# RTDsSheet2.net
KiCad netlist of a schematic drawn in Altium Designer
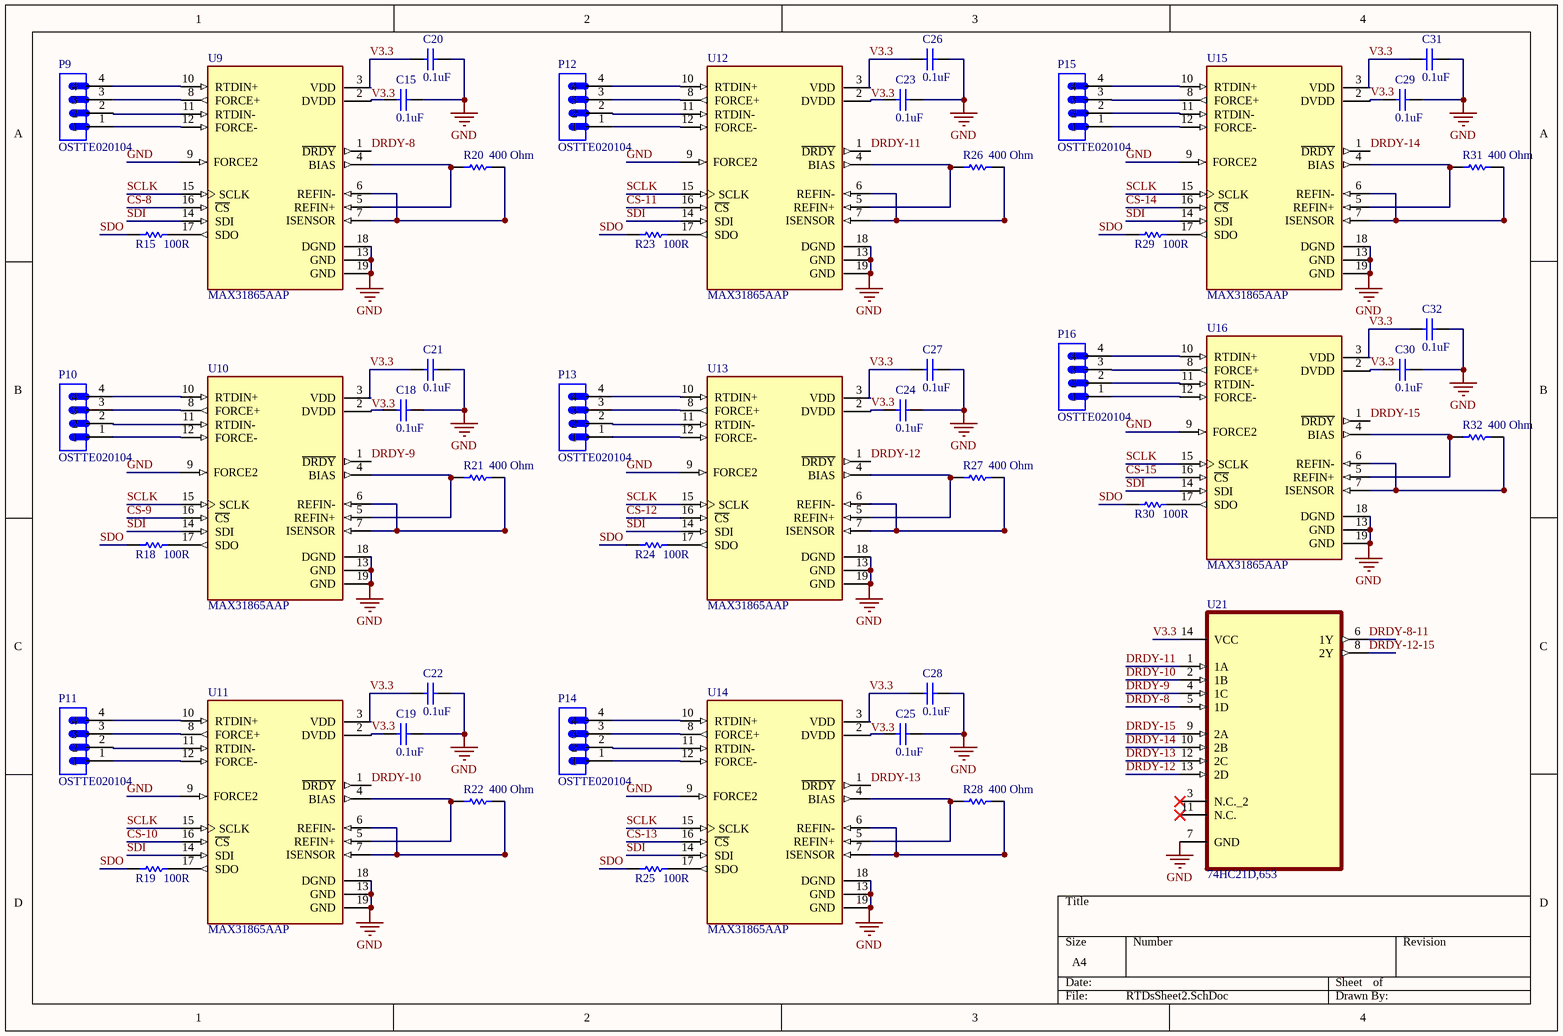
[diagram p0: RTDsSheet2.SchDoc]

(export (version "E")
  (design (tool "Eeschema 10.0.6"))
  (components
    (comp (ref "C15")
      (value "0.1uF")
      (footprint "1608[0603]")
      (description "Capacitor (Semiconductor SIM Model)")
      (fields (field (name "PUBLISHER") "Altium Limited"))
      (libsource (lib "Miscellaneous Devices") (part "Cap Semi"))
    )
    (comp (ref "C18")
      (value "0.1uF")
      (footprint "1608[0603]")
      (description "Capacitor (Semiconductor SIM Model)")
      (fields (field (name "PUBLISHER") "Altium Limited"))
      (libsource (lib "Miscellaneous Devices") (part "Cap Semi"))
    )
    (comp (ref "C19")
      (value "0.1uF")
      (footprint "1608[0603]")
      (description "Capacitor (Semiconductor SIM Model)")
      (fields (field (name "PUBLISHER") "Altium Limited"))
      (libsource (lib "Miscellaneous Devices") (part "Cap Semi"))
    )
    (comp (ref "C20")
      (value "0.1uF")
      (footprint "1608[0603]")
      (description "Capacitor (Semiconductor SIM Model)")
      (fields (field (name "PUBLISHER") "Altium Limited"))
      (libsource (lib "Miscellaneous Devices") (part "Cap Semi"))
    )
    (comp (ref "C21")
      (value "0.1uF")
      (footprint "1608[0603]")
      (description "Capacitor (Semiconductor SIM Model)")
      (fields (field (name "PUBLISHER") "Altium Limited"))
      (libsource (lib "Miscellaneous Devices") (part "Cap Semi"))
    )
    (comp (ref "C22")
      (value "0.1uF")
      (footprint "1608[0603]")
      (description "Capacitor (Semiconductor SIM Model)")
      (fields (field (name "PUBLISHER") "Altium Limited"))
      (libsource (lib "Miscellaneous Devices") (part "Cap Semi"))
    )
    (comp (ref "C23")
      (value "0.1uF")
      (footprint "1608[0603]")
      (description "Capacitor (Semiconductor SIM Model)")
      (fields (field (name "PUBLISHER") "Altium Limited"))
      (libsource (lib "Miscellaneous Devices") (part "Cap Semi"))
    )
    (comp (ref "C24")
      (value "0.1uF")
      (footprint "1608[0603]")
      (description "Capacitor (Semiconductor SIM Model)")
      (fields (field (name "PUBLISHER") "Altium Limited"))
      (libsource (lib "Miscellaneous Devices") (part "Cap Semi"))
    )
    (comp (ref "C25")
      (value "0.1uF")
      (footprint "1608[0603]")
      (description "Capacitor (Semiconductor SIM Model)")
      (fields (field (name "PUBLISHER") "Altium Limited"))
      (libsource (lib "Miscellaneous Devices") (part "Cap Semi"))
    )
    (comp (ref "C26")
      (value "0.1uF")
      (footprint "1608[0603]")
      (description "Capacitor (Semiconductor SIM Model)")
      (fields (field (name "PUBLISHER") "Altium Limited"))
      (libsource (lib "Miscellaneous Devices") (part "Cap Semi"))
    )
    (comp (ref "C27")
      (value "0.1uF")
      (footprint "1608[0603]")
      (description "Capacitor (Semiconductor SIM Model)")
      (fields (field (name "PUBLISHER") "Altium Limited"))
      (libsource (lib "Miscellaneous Devices") (part "Cap Semi"))
    )
    (comp (ref "C28")
      (value "0.1uF")
      (footprint "1608[0603]")
      (description "Capacitor (Semiconductor SIM Model)")
      (fields (field (name "PUBLISHER") "Altium Limited"))
      (libsource (lib "Miscellaneous Devices") (part "Cap Semi"))
    )
    (comp (ref "C29")
      (value "0.1uF")
      (footprint "1608[0603]")
      (description "Capacitor (Semiconductor SIM Model)")
      (fields (field (name "PUBLISHER") "Altium Limited"))
      (libsource (lib "Miscellaneous Devices") (part "Cap Semi"))
    )
    (comp (ref "C30")
      (value "0.1uF")
      (footprint "1608[0603]")
      (description "Capacitor (Semiconductor SIM Model)")
      (fields (field (name "PUBLISHER") "Altium Limited"))
      (libsource (lib "Miscellaneous Devices") (part "Cap Semi"))
    )
    (comp (ref "C31")
      (value "0.1uF")
      (footprint "1608[0603]")
      (description "Capacitor (Semiconductor SIM Model)")
      (fields (field (name "PUBLISHER") "Altium Limited"))
      (libsource (lib "Miscellaneous Devices") (part "Cap Semi"))
    )
    (comp (ref "C32")
      (value "0.1uF")
      (footprint "1608[0603]")
      (description "Capacitor (Semiconductor SIM Model)")
      (fields (field (name "PUBLISHER") "Altium Limited"))
      (libsource (lib "Miscellaneous Devices") (part "Cap Semi"))
    )
    (comp (ref "P9")
      (value "OSTTE020104")
      (footprint "3-641209-4:TE_3-641209-4")
      (description "Terminal Block 3.5mm 2pos Pcb")
      (fields (field (name "MF") "{'manufacturer': u'On Shore'}"))
      (libsource (lib "OSTTE040104") (part "OSTTE020104"))
    )
    (comp (ref "P10")
      (value "OSTTE020104")
      (footprint "3-641209-4:TE_3-641209-4")
      (description "Terminal Block 3.5mm 2pos Pcb")
      (fields (field (name "MF") "{'manufacturer': u'On Shore'}"))
      (libsource (lib "OSTTE040104") (part "OSTTE020104"))
    )
    (comp (ref "P11")
      (value "OSTTE020104")
      (footprint "3-641209-4:TE_3-641209-4")
      (description "Terminal Block 3.5mm 2pos Pcb")
      (fields (field (name "MF") "{'manufacturer': u'On Shore'}"))
      (libsource (lib "OSTTE040104") (part "OSTTE020104"))
    )
    (comp (ref "P12")
      (value "OSTTE020104")
      (footprint "3-641209-4:TE_3-641209-4")
      (description "Terminal Block 3.5mm 2pos Pcb")
      (fields (field (name "MF") "{'manufacturer': u'On Shore'}"))
      (libsource (lib "OSTTE040104") (part "OSTTE020104"))
    )
    (comp (ref "P13")
      (value "OSTTE020104")
      (footprint "3-641209-4:TE_3-641209-4")
      (description "Terminal Block 3.5mm 2pos Pcb")
      (fields (field (name "MF") "{'manufacturer': u'On Shore'}"))
      (libsource (lib "OSTTE040104") (part "OSTTE020104"))
    )
    (comp (ref "P14")
      (value "OSTTE020104")
      (footprint "3-641209-4:TE_3-641209-4")
      (description "Terminal Block 3.5mm 2pos Pcb")
      (fields (field (name "MF") "{'manufacturer': u'On Shore'}"))
      (libsource (lib "OSTTE040104") (part "OSTTE020104"))
    )
    (comp (ref "P15")
      (value "OSTTE020104")
      (footprint "3-641209-4:TE_3-641209-4")
      (description "Terminal Block 3.5mm 2pos Pcb")
      (fields (field (name "MF") "{'manufacturer': u'On Shore'}"))
      (libsource (lib "OSTTE040104") (part "OSTTE020104"))
    )
    (comp (ref "P16")
      (value "OSTTE020104")
      (footprint "3-641209-4:TE_3-641209-4")
      (description "Terminal Block 3.5mm 2pos Pcb")
      (fields (field (name "MF") "{'manufacturer': u'On Shore'}"))
      (libsource (lib "OSTTE040104") (part "OSTTE020104"))
    )
    (comp (ref "R15")
      (value "100R")
      (footprint "1608[0603]")
      (description "Semiconductor Resistor")
      (fields (field (name "PUBLISHER") "Altium Limited"))
      (libsource (lib "Miscellaneous Devices") (part "Res Semi"))
    )
    (comp (ref "R18")
      (value "100R")
      (footprint "1608[0603]")
      (description "Semiconductor Resistor")
      (fields (field (name "PUBLISHER") "Altium Limited"))
      (libsource (lib "Miscellaneous Devices") (part "Res Semi"))
    )
    (comp (ref "R19")
      (value "100R")
      (footprint "1608[0603]")
      (description "Semiconductor Resistor")
      (fields (field (name "PUBLISHER") "Altium Limited"))
      (libsource (lib "Miscellaneous Devices") (part "Res Semi"))
    )
    (comp (ref "R20")
      (value "400 Ohm")
      (footprint "6-0805_M")
      (description "Semiconductor Resistor")
      (fields (field (name "PUBLISHER") "Altium Limited"))
      (libsource (lib "Miscellaneous Devices") (part "Res Semi"))
    )
    (comp (ref "R21")
      (value "400 Ohm")
      (footprint "6-0805_M")
      (description "Semiconductor Resistor")
      (fields (field (name "PUBLISHER") "Altium Limited"))
      (libsource (lib "Miscellaneous Devices") (part "Res Semi"))
    )
    (comp (ref "R22")
      (value "400 Ohm")
      (footprint "6-0805_M")
      (description "Semiconductor Resistor")
      (fields (field (name "PUBLISHER") "Altium Limited"))
      (libsource (lib "Miscellaneous Devices") (part "Res Semi"))
    )
    (comp (ref "R23")
      (value "100R")
      (footprint "1608[0603]")
      (description "Semiconductor Resistor")
      (fields (field (name "PUBLISHER") "Altium Limited"))
      (libsource (lib "Miscellaneous Devices") (part "Res Semi"))
    )
    (comp (ref "R24")
      (value "100R")
      (footprint "1608[0603]")
      (description "Semiconductor Resistor")
      (fields (field (name "PUBLISHER") "Altium Limited"))
      (libsource (lib "Miscellaneous Devices") (part "Res Semi"))
    )
    (comp (ref "R25")
      (value "100R")
      (footprint "1608[0603]")
      (description "Semiconductor Resistor")
      (fields (field (name "PUBLISHER") "Altium Limited"))
      (libsource (lib "Miscellaneous Devices") (part "Res Semi"))
    )
    (comp (ref "R26")
      (value "400 Ohm")
      (footprint "6-0805_M")
      (description "Semiconductor Resistor")
      (fields (field (name "PUBLISHER") "Altium Limited"))
      (libsource (lib "Miscellaneous Devices") (part "Res Semi"))
    )
    (comp (ref "R27")
      (value "400 Ohm")
      (footprint "6-0805_M")
      (description "Semiconductor Resistor")
      (fields (field (name "PUBLISHER") "Altium Limited"))
      (libsource (lib "Miscellaneous Devices") (part "Res Semi"))
    )
    (comp (ref "R28")
      (value "400 Ohm")
      (footprint "6-0805_M")
      (description "Semiconductor Resistor")
      (fields (field (name "PUBLISHER") "Altium Limited"))
      (libsource (lib "Miscellaneous Devices") (part "Res Semi"))
    )
    (comp (ref "R29")
      (value "100R")
      (footprint "1608[0603]")
      (description "Semiconductor Resistor")
      (fields (field (name "PUBLISHER") "Altium Limited"))
      (libsource (lib "Miscellaneous Devices") (part "Res Semi"))
    )
    (comp (ref "R30")
      (value "100R")
      (footprint "1608[0603]")
      (description "Semiconductor Resistor")
      (fields (field (name "PUBLISHER") "Altium Limited"))
      (libsource (lib "Miscellaneous Devices") (part "Res Semi"))
    )
    (comp (ref "R31")
      (value "400 Ohm")
      (footprint "6-0805_M")
      (description "Semiconductor Resistor")
      (fields (field (name "PUBLISHER") "Altium Limited"))
      (libsource (lib "Miscellaneous Devices") (part "Res Semi"))
    )
    (comp (ref "R32")
      (value "400 Ohm")
      (footprint "6-0805_M")
      (description "Semiconductor Resistor")
      (fields (field (name "PUBLISHER") "Altium Limited"))
      (libsource (lib "Miscellaneous Devices") (part "Res Semi"))
    )
    (comp (ref "U9")
      (value "MAX31865AAP")
      (footprint "MAX31865AAP+:SOP65P777X199-20N")
      (description "Rtd To Digital Converter In Ssop Tr")
      (fields (field (name "MF") "{'manufacturer': u'Maxim Integrated'}"))
      (libsource (lib "MAX31865AAP+") (part "MAX31865AAP"))
    )
    (comp (ref "U10")
      (value "MAX31865AAP")
      (footprint "MAX31865AAP+:SOP65P777X199-20N")
      (description "Rtd To Digital Converter In Ssop Tr")
      (fields (field (name "MF") "{'manufacturer': u'Maxim Integrated'}"))
      (libsource (lib "MAX31865AAP+") (part "MAX31865AAP"))
    )
    (comp (ref "U11")
      (value "MAX31865AAP")
      (footprint "MAX31865AAP+:SOP65P777X199-20N")
      (description "Rtd To Digital Converter In Ssop Tr")
      (fields (field (name "MF") "{'manufacturer': u'Maxim Integrated'}"))
      (libsource (lib "MAX31865AAP+") (part "MAX31865AAP"))
    )
    (comp (ref "U12")
      (value "MAX31865AAP")
      (footprint "MAX31865AAP+:SOP65P777X199-20N")
      (description "Rtd To Digital Converter In Ssop Tr")
      (fields (field (name "MF") "{'manufacturer': u'Maxim Integrated'}"))
      (libsource (lib "MAX31865AAP+") (part "MAX31865AAP"))
    )
    (comp (ref "U13")
      (value "MAX31865AAP")
      (footprint "MAX31865AAP+:SOP65P777X199-20N")
      (description "Rtd To Digital Converter In Ssop Tr")
      (fields (field (name "MF") "{'manufacturer': u'Maxim Integrated'}"))
      (libsource (lib "MAX31865AAP+") (part "MAX31865AAP"))
    )
    (comp (ref "U14")
      (value "MAX31865AAP")
      (footprint "MAX31865AAP+:SOP65P777X199-20N")
      (description "Rtd To Digital Converter In Ssop Tr")
      (fields (field (name "MF") "{'manufacturer': u'Maxim Integrated'}"))
      (libsource (lib "MAX31865AAP+") (part "MAX31865AAP"))
    )
    (comp (ref "U15")
      (value "MAX31865AAP")
      (footprint "MAX31865AAP+:SOP65P777X199-20N")
      (description "Rtd To Digital Converter In Ssop Tr")
      (fields (field (name "MF") "{'manufacturer': u'Maxim Integrated'}"))
      (libsource (lib "MAX31865AAP+") (part "MAX31865AAP"))
    )
    (comp (ref "U16")
      (value "MAX31865AAP")
      (footprint "MAX31865AAP+:SOP65P777X199-20N")
      (description "Rtd To Digital Converter In Ssop Tr")
      (fields (field (name "MF") "{'manufacturer': u'Maxim Integrated'}"))
      (libsource (lib "MAX31865AAP+") (part "MAX31865AAP"))
    )
    (comp (ref "U21")
      (value "74HC21D,653")
      (footprint "74HC21D,653:SOIC127P600X175-14N")
      (description "Dual 4-input AND gate")
      (fields (field (name "MF") "{'manufacturer': u'Nexperia USA'}"))
      (libsource (lib "*") (part "74HC21D,653"))
    )
  )
  (nets
    (net (code "1") (name "/CS-8") (class "Default")
      (node (ref "U9") (pin "16") (pinfunction "~{CS}_16") (pintype "input"))
    )
    (net (code "2") (name "/CS-9") (class "Default")
      (node (ref "U10") (pin "16") (pinfunction "~{CS}_16") (pintype "input"))
    )
    (net (code "3") (name "/CS-10") (class "Default")
      (node (ref "U11") (pin "16") (pinfunction "~{CS}_16") (pintype "input"))
    )
    (net (code "4") (name "/CS-11") (class "Default")
      (node (ref "U12") (pin "16") (pinfunction "~{CS}_16") (pintype "input"))
    )
    (net (code "5") (name "/CS-12") (class "Default")
      (node (ref "U13") (pin "16") (pinfunction "~{CS}_16") (pintype "input"))
    )
    (net (code "6") (name "/CS-13") (class "Default")
      (node (ref "U14") (pin "16") (pinfunction "~{CS}_16") (pintype "input"))
    )
    (net (code "7") (name "/CS-14") (class "Default")
      (node (ref "U15") (pin "16") (pinfunction "~{CS}_16") (pintype "input"))
    )
    (net (code "8") (name "/CS-15") (class "Default")
      (node (ref "U16") (pin "16") (pinfunction "~{CS}_16") (pintype "input"))
    )
    (net (code "9") (name "/DRDY-8") (class "Default")
      (node (ref "U21") (pin "5") (pinfunction "1D_5") (pintype "input"))
      (node (ref "U9") (pin "1") (pinfunction "~{DRDY}_1") (pintype "output"))
    )
    (net (code "10") (name "/DRDY-8-11") (class "Default")
      (node (ref "U21") (pin "6") (pinfunction "1Y_6") (pintype "output"))
    )
    (net (code "11") (name "/DRDY-9") (class "Default")
      (node (ref "U10") (pin "1") (pinfunction "~{DRDY}_1") (pintype "output"))
      (node (ref "U21") (pin "4") (pinfunction "1C_4") (pintype "input"))
    )
    (net (code "12") (name "/DRDY-10") (class "Default")
      (node (ref "U11") (pin "1") (pinfunction "~{DRDY}_1") (pintype "output"))
      (node (ref "U21") (pin "2") (pinfunction "1B_2") (pintype "input"))
    )
    (net (code "13") (name "/DRDY-11") (class "Default")
      (node (ref "U12") (pin "1") (pinfunction "~{DRDY}_1") (pintype "output"))
      (node (ref "U21") (pin "1") (pinfunction "1A_1") (pintype "input"))
    )
    (net (code "14") (name "/DRDY-12") (class "Default")
      (node (ref "U13") (pin "1") (pinfunction "~{DRDY}_1") (pintype "output"))
      (node (ref "U21") (pin "13") (pinfunction "2D_13") (pintype "input"))
    )
    (net (code "15") (name "/DRDY-12-15") (class "Default")
      (node (ref "U21") (pin "8") (pinfunction "2Y_8") (pintype "output"))
    )
    (net (code "16") (name "/DRDY-13") (class "Default")
      (node (ref "U14") (pin "1") (pinfunction "~{DRDY}_1") (pintype "output"))
      (node (ref "U21") (pin "12") (pinfunction "2C_12") (pintype "input"))
    )
    (net (code "17") (name "/DRDY-14") (class "Default")
      (node (ref "U15") (pin "1") (pinfunction "~{DRDY}_1") (pintype "output"))
      (node (ref "U21") (pin "10") (pinfunction "2B_10") (pintype "input"))
    )
    (net (code "18") (name "/DRDY-15") (class "Default")
      (node (ref "U16") (pin "1") (pinfunction "~{DRDY}_1") (pintype "output"))
      (node (ref "U21") (pin "9") (pinfunction "2A_9") (pintype "input"))
    )
    (net (code "19") (name "/SCLK") (class "Default")
      (node (ref "U10") (pin "15") (pinfunction "SCLK_15") (pintype "input"))
      (node (ref "U11") (pin "15") (pinfunction "SCLK_15") (pintype "input"))
      (node (ref "U12") (pin "15") (pinfunction "SCLK_15") (pintype "input"))
      (node (ref "U13") (pin "15") (pinfunction "SCLK_15") (pintype "input"))
      (node (ref "U14") (pin "15") (pinfunction "SCLK_15") (pintype "input"))
      (node (ref "U15") (pin "15") (pinfunction "SCLK_15") (pintype "input"))
      (node (ref "U16") (pin "15") (pinfunction "SCLK_15") (pintype "input"))
      (node (ref "U9") (pin "15") (pinfunction "SCLK_15") (pintype "input"))
    )
    (net (code "20") (name "/SDI") (class "Default")
      (node (ref "U10") (pin "14") (pinfunction "SDI_14") (pintype "input"))
      (node (ref "U11") (pin "14") (pinfunction "SDI_14") (pintype "input"))
      (node (ref "U12") (pin "14") (pinfunction "SDI_14") (pintype "input"))
      (node (ref "U13") (pin "14") (pinfunction "SDI_14") (pintype "input"))
      (node (ref "U14") (pin "14") (pinfunction "SDI_14") (pintype "input"))
      (node (ref "U15") (pin "14") (pinfunction "SDI_14") (pintype "input"))
      (node (ref "U16") (pin "14") (pinfunction "SDI_14") (pintype "input"))
      (node (ref "U9") (pin "14") (pinfunction "SDI_14") (pintype "input"))
    )
    (net (code "21") (name "/SDO") (class "Default")
      (node (ref "R15") (pin "2") (pinfunction "2_2") (pintype "passive"))
      (node (ref "R18") (pin "2") (pinfunction "2_2") (pintype "passive"))
      (node (ref "R19") (pin "2") (pinfunction "2_2") (pintype "passive"))
      (node (ref "R23") (pin "2") (pinfunction "2_2") (pintype "passive"))
      (node (ref "R24") (pin "2") (pinfunction "2_2") (pintype "passive"))
      (node (ref "R25") (pin "2") (pinfunction "2_2") (pintype "passive"))
      (node (ref "R29") (pin "2") (pinfunction "2_2") (pintype "passive"))
      (node (ref "R30") (pin "2") (pinfunction "2_2") (pintype "passive"))
    )
    (net (code "22") (name "/V3.3") (class "Default")
      (node (ref "C15") (pin "2") (pinfunction "2_2") (pintype "passive"))
      (node (ref "C18") (pin "2") (pinfunction "2_2") (pintype "passive"))
      (node (ref "C19") (pin "2") (pinfunction "2_2") (pintype "passive"))
      (node (ref "C20") (pin "2") (pinfunction "2_2") (pintype "passive"))
      (node (ref "C21") (pin "2") (pinfunction "2_2") (pintype "passive"))
      (node (ref "C22") (pin "2") (pinfunction "2_2") (pintype "passive"))
      (node (ref "C23") (pin "2") (pinfunction "2_2") (pintype "passive"))
      (node (ref "C24") (pin "2") (pinfunction "2_2") (pintype "passive"))
      (node (ref "C25") (pin "2") (pinfunction "2_2") (pintype "passive"))
      (node (ref "C26") (pin "2") (pinfunction "2_2") (pintype "passive"))
      (node (ref "C27") (pin "2") (pinfunction "2_2") (pintype "passive"))
      (node (ref "C28") (pin "2") (pinfunction "2_2") (pintype "passive"))
      (node (ref "C29") (pin "2") (pinfunction "2_2") (pintype "passive"))
      (node (ref "C30") (pin "2") (pinfunction "2_2") (pintype "passive"))
      (node (ref "C31") (pin "2") (pinfunction "2_2") (pintype "passive"))
      (node (ref "C32") (pin "2") (pinfunction "2_2") (pintype "passive"))
      (node (ref "U10") (pin "2") (pinfunction "DVDD_2") (pintype "power_in"))
      (node (ref "U10") (pin "3") (pinfunction "VDD_3") (pintype "power_in"))
      (node (ref "U11") (pin "2") (pinfunction "DVDD_2") (pintype "power_in"))
      (node (ref "U11") (pin "3") (pinfunction "VDD_3") (pintype "power_in"))
      (node (ref "U12") (pin "2") (pinfunction "DVDD_2") (pintype "power_in"))
      (node (ref "U12") (pin "3") (pinfunction "VDD_3") (pintype "power_in"))
      (node (ref "U13") (pin "2") (pinfunction "DVDD_2") (pintype "power_in"))
      (node (ref "U13") (pin "3") (pinfunction "VDD_3") (pintype "power_in"))
      (node (ref "U14") (pin "2") (pinfunction "DVDD_2") (pintype "power_in"))
      (node (ref "U14") (pin "3") (pinfunction "VDD_3") (pintype "power_in"))
      (node (ref "U15") (pin "2") (pinfunction "DVDD_2") (pintype "power_in"))
      (node (ref "U15") (pin "3") (pinfunction "VDD_3") (pintype "power_in"))
      (node (ref "U16") (pin "2") (pinfunction "DVDD_2") (pintype "power_in"))
      (node (ref "U16") (pin "3") (pinfunction "VDD_3") (pintype "power_in"))
      (node (ref "U21") (pin "14") (pinfunction "VCC_14") (pintype "power_in"))
      (node (ref "U9") (pin "2") (pinfunction "DVDD_2") (pintype "power_in"))
      (node (ref "U9") (pin "3") (pinfunction "VDD_3") (pintype "power_in"))
    )
    (net (code "23") (name "GND") (class "Default")
      (node (ref "C15") (pin "1") (pinfunction "1_1") (pintype "passive"))
      (node (ref "C18") (pin "1") (pinfunction "1_1") (pintype "passive"))
      (node (ref "C19") (pin "1") (pinfunction "1_1") (pintype "passive"))
      (node (ref "C20") (pin "1") (pinfunction "1_1") (pintype "passive"))
      (node (ref "C21") (pin "1") (pinfunction "1_1") (pintype "passive"))
      (node (ref "C22") (pin "1") (pinfunction "1_1") (pintype "passive"))
      (node (ref "C23") (pin "1") (pinfunction "1_1") (pintype "passive"))
      (node (ref "C24") (pin "1") (pinfunction "1_1") (pintype "passive"))
      (node (ref "C25") (pin "1") (pinfunction "1_1") (pintype "passive"))
      (node (ref "C26") (pin "1") (pinfunction "1_1") (pintype "passive"))
      (node (ref "C27") (pin "1") (pinfunction "1_1") (pintype "passive"))
      (node (ref "C28") (pin "1") (pinfunction "1_1") (pintype "passive"))
      (node (ref "C29") (pin "1") (pinfunction "1_1") (pintype "passive"))
      (node (ref "C30") (pin "1") (pinfunction "1_1") (pintype "passive"))
      (node (ref "C31") (pin "1") (pinfunction "1_1") (pintype "passive"))
      (node (ref "C32") (pin "1") (pinfunction "1_1") (pintype "passive"))
      (node (ref "U10") (pin "13") (pinfunction "GND_13") (pintype "power_in"))
      (node (ref "U10") (pin "18") (pinfunction "DGND_18") (pintype "power_in"))
      (node (ref "U10") (pin "19") (pinfunction "GND_19") (pintype "power_in"))
      (node (ref "U10") (pin "9") (pinfunction "FORCE2_9") (pintype "input"))
      (node (ref "U11") (pin "13") (pinfunction "GND_13") (pintype "power_in"))
      (node (ref "U11") (pin "18") (pinfunction "DGND_18") (pintype "power_in"))
      (node (ref "U11") (pin "19") (pinfunction "GND_19") (pintype "power_in"))
      (node (ref "U11") (pin "9") (pinfunction "FORCE2_9") (pintype "input"))
      (node (ref "U12") (pin "13") (pinfunction "GND_13") (pintype "power_in"))
      (node (ref "U12") (pin "18") (pinfunction "DGND_18") (pintype "power_in"))
      (node (ref "U12") (pin "19") (pinfunction "GND_19") (pintype "power_in"))
      (node (ref "U12") (pin "9") (pinfunction "FORCE2_9") (pintype "input"))
      (node (ref "U13") (pin "13") (pinfunction "GND_13") (pintype "power_in"))
      (node (ref "U13") (pin "18") (pinfunction "DGND_18") (pintype "power_in"))
      (node (ref "U13") (pin "19") (pinfunction "GND_19") (pintype "power_in"))
      (node (ref "U13") (pin "9") (pinfunction "FORCE2_9") (pintype "input"))
      (node (ref "U14") (pin "13") (pinfunction "GND_13") (pintype "power_in"))
      (node (ref "U14") (pin "18") (pinfunction "DGND_18") (pintype "power_in"))
      (node (ref "U14") (pin "19") (pinfunction "GND_19") (pintype "power_in"))
      (node (ref "U14") (pin "9") (pinfunction "FORCE2_9") (pintype "input"))
      (node (ref "U15") (pin "13") (pinfunction "GND_13") (pintype "power_in"))
      (node (ref "U15") (pin "18") (pinfunction "DGND_18") (pintype "power_in"))
      (node (ref "U15") (pin "19") (pinfunction "GND_19") (pintype "power_in"))
      (node (ref "U15") (pin "9") (pinfunction "FORCE2_9") (pintype "input"))
      (node (ref "U16") (pin "13") (pinfunction "GND_13") (pintype "power_in"))
      (node (ref "U16") (pin "18") (pinfunction "DGND_18") (pintype "power_in"))
      (node (ref "U16") (pin "19") (pinfunction "GND_19") (pintype "power_in"))
      (node (ref "U16") (pin "9") (pinfunction "FORCE2_9") (pintype "input"))
      (node (ref "U21") (pin "7") (pinfunction "GND_7") (pintype "passive"))
      (node (ref "U9") (pin "13") (pinfunction "GND_13") (pintype "power_in"))
      (node (ref "U9") (pin "18") (pinfunction "DGND_18") (pintype "power_in"))
      (node (ref "U9") (pin "19") (pinfunction "GND_19") (pintype "power_in"))
      (node (ref "U9") (pin "9") (pinfunction "FORCE2_9") (pintype "input"))
    )
    (net (code "24") (name "Net-(U9-BIAS)") (class "Default")
      (node (ref "R20") (pin "2") (pinfunction "2_2") (pintype "passive"))
      (node (ref "U9") (pin "4") (pinfunction "BIAS_4") (pintype "output"))
      (node (ref "U9") (pin "5") (pinfunction "REFIN+_5") (pintype "input"))
    )
    (net (code "25") (name "Net-(U9-FORCE+)") (class "Default")
      (node (ref "P9") (pin "3") (pinfunction "3_3") (pintype "passive"))
      (node (ref "U9") (pin "8") (pinfunction "FORCE+_8") (pintype "output"))
    )
    (net (code "26") (name "Net-(U9-FORCE-)") (class "Default")
      (node (ref "P9") (pin "1") (pinfunction "1_1") (pintype "passive"))
      (node (ref "U9") (pin "12") (pinfunction "FORCE-_12") (pintype "input"))
    )
    (net (code "27") (name "Net-(U9-ISENSOR)") (class "Default")
      (node (ref "R20") (pin "1") (pinfunction "1_1") (pintype "passive"))
      (node (ref "U9") (pin "6") (pinfunction "REFIN-_6") (pintype "input"))
      (node (ref "U9") (pin "7") (pinfunction "ISENSOR_7") (pintype "input"))
    )
    (net (code "28") (name "Net-(U9-RTDIN+)") (class "Default")
      (node (ref "P9") (pin "4") (pinfunction "4_4") (pintype "passive"))
      (node (ref "U9") (pin "10") (pinfunction "RTDIN+_10") (pintype "input"))
    )
    (net (code "29") (name "Net-(U9-RTDIN-)") (class "Default")
      (node (ref "P9") (pin "2") (pinfunction "2_2") (pintype "passive"))
      (node (ref "U9") (pin "11") (pinfunction "RTDIN-_11") (pintype "input"))
    )
    (net (code "30") (name "Net-(U9-SDO)") (class "Default")
      (node (ref "R15") (pin "1") (pinfunction "1_1") (pintype "passive"))
      (node (ref "U9") (pin "17") (pinfunction "SDO_17") (pintype "output"))
    )
    (net (code "31") (name "Net-(U10-BIAS)") (class "Default")
      (node (ref "R21") (pin "2") (pinfunction "2_2") (pintype "passive"))
      (node (ref "U10") (pin "4") (pinfunction "BIAS_4") (pintype "output"))
      (node (ref "U10") (pin "5") (pinfunction "REFIN+_5") (pintype "input"))
    )
    (net (code "32") (name "Net-(U10-FORCE+)") (class "Default")
      (node (ref "P10") (pin "3") (pinfunction "3_3") (pintype "passive"))
      (node (ref "U10") (pin "8") (pinfunction "FORCE+_8") (pintype "output"))
    )
    (net (code "33") (name "Net-(U10-FORCE-)") (class "Default")
      (node (ref "P10") (pin "1") (pinfunction "1_1") (pintype "passive"))
      (node (ref "U10") (pin "12") (pinfunction "FORCE-_12") (pintype "input"))
    )
    (net (code "34") (name "Net-(U10-ISENSOR)") (class "Default")
      (node (ref "R21") (pin "1") (pinfunction "1_1") (pintype "passive"))
      (node (ref "U10") (pin "6") (pinfunction "REFIN-_6") (pintype "input"))
      (node (ref "U10") (pin "7") (pinfunction "ISENSOR_7") (pintype "input"))
    )
    (net (code "35") (name "Net-(U10-RTDIN+)") (class "Default")
      (node (ref "P10") (pin "4") (pinfunction "4_4") (pintype "passive"))
      (node (ref "U10") (pin "10") (pinfunction "RTDIN+_10") (pintype "input"))
    )
    (net (code "36") (name "Net-(U10-RTDIN-)") (class "Default")
      (node (ref "P10") (pin "2") (pinfunction "2_2") (pintype "passive"))
      (node (ref "U10") (pin "11") (pinfunction "RTDIN-_11") (pintype "input"))
    )
    (net (code "37") (name "Net-(U10-SDO)") (class "Default")
      (node (ref "R18") (pin "1") (pinfunction "1_1") (pintype "passive"))
      (node (ref "U10") (pin "17") (pinfunction "SDO_17") (pintype "output"))
    )
    (net (code "38") (name "Net-(U11-BIAS)") (class "Default")
      (node (ref "R22") (pin "2") (pinfunction "2_2") (pintype "passive"))
      (node (ref "U11") (pin "4") (pinfunction "BIAS_4") (pintype "output"))
      (node (ref "U11") (pin "5") (pinfunction "REFIN+_5") (pintype "input"))
    )
    (net (code "39") (name "Net-(U11-FORCE+)") (class "Default")
      (node (ref "P11") (pin "3") (pinfunction "3_3") (pintype "passive"))
      (node (ref "U11") (pin "8") (pinfunction "FORCE+_8") (pintype "output"))
    )
    (net (code "40") (name "Net-(U11-FORCE-)") (class "Default")
      (node (ref "P11") (pin "1") (pinfunction "1_1") (pintype "passive"))
      (node (ref "U11") (pin "12") (pinfunction "FORCE-_12") (pintype "input"))
    )
    (net (code "41") (name "Net-(U11-ISENSOR)") (class "Default")
      (node (ref "R22") (pin "1") (pinfunction "1_1") (pintype "passive"))
      (node (ref "U11") (pin "6") (pinfunction "REFIN-_6") (pintype "input"))
      (node (ref "U11") (pin "7") (pinfunction "ISENSOR_7") (pintype "input"))
    )
    (net (code "42") (name "Net-(U11-RTDIN+)") (class "Default")
      (node (ref "P11") (pin "4") (pinfunction "4_4") (pintype "passive"))
      (node (ref "U11") (pin "10") (pinfunction "RTDIN+_10") (pintype "input"))
    )
    (net (code "43") (name "Net-(U11-RTDIN-)") (class "Default")
      (node (ref "P11") (pin "2") (pinfunction "2_2") (pintype "passive"))
      (node (ref "U11") (pin "11") (pinfunction "RTDIN-_11") (pintype "input"))
    )
    (net (code "44") (name "Net-(U11-SDO)") (class "Default")
      (node (ref "R19") (pin "1") (pinfunction "1_1") (pintype "passive"))
      (node (ref "U11") (pin "17") (pinfunction "SDO_17") (pintype "output"))
    )
    (net (code "45") (name "Net-(U12-BIAS)") (class "Default")
      (node (ref "R26") (pin "2") (pinfunction "2_2") (pintype "passive"))
      (node (ref "U12") (pin "4") (pinfunction "BIAS_4") (pintype "output"))
      (node (ref "U12") (pin "5") (pinfunction "REFIN+_5") (pintype "input"))
    )
    (net (code "46") (name "Net-(U12-FORCE+)") (class "Default")
      (node (ref "P12") (pin "3") (pinfunction "3_3") (pintype "passive"))
      (node (ref "U12") (pin "8") (pinfunction "FORCE+_8") (pintype "output"))
    )
    (net (code "47") (name "Net-(U12-FORCE-)") (class "Default")
      (node (ref "P12") (pin "1") (pinfunction "1_1") (pintype "passive"))
      (node (ref "U12") (pin "12") (pinfunction "FORCE-_12") (pintype "input"))
    )
    (net (code "48") (name "Net-(U12-ISENSOR)") (class "Default")
      (node (ref "R26") (pin "1") (pinfunction "1_1") (pintype "passive"))
      (node (ref "U12") (pin "6") (pinfunction "REFIN-_6") (pintype "input"))
      (node (ref "U12") (pin "7") (pinfunction "ISENSOR_7") (pintype "input"))
    )
    (net (code "49") (name "Net-(U12-RTDIN+)") (class "Default")
      (node (ref "P12") (pin "4") (pinfunction "4_4") (pintype "passive"))
      (node (ref "U12") (pin "10") (pinfunction "RTDIN+_10") (pintype "input"))
    )
    (net (code "50") (name "Net-(U12-RTDIN-)") (class "Default")
      (node (ref "P12") (pin "2") (pinfunction "2_2") (pintype "passive"))
      (node (ref "U12") (pin "11") (pinfunction "RTDIN-_11") (pintype "input"))
    )
    (net (code "51") (name "Net-(U12-SDO)") (class "Default")
      (node (ref "R23") (pin "1") (pinfunction "1_1") (pintype "passive"))
      (node (ref "U12") (pin "17") (pinfunction "SDO_17") (pintype "output"))
    )
    (net (code "52") (name "Net-(U13-BIAS)") (class "Default")
      (node (ref "R27") (pin "2") (pinfunction "2_2") (pintype "passive"))
      (node (ref "U13") (pin "4") (pinfunction "BIAS_4") (pintype "output"))
      (node (ref "U13") (pin "5") (pinfunction "REFIN+_5") (pintype "input"))
    )
    (net (code "53") (name "Net-(U13-FORCE+)") (class "Default")
      (node (ref "P13") (pin "3") (pinfunction "3_3") (pintype "passive"))
      (node (ref "U13") (pin "8") (pinfunction "FORCE+_8") (pintype "output"))
    )
    (net (code "54") (name "Net-(U13-FORCE-)") (class "Default")
      (node (ref "P13") (pin "1") (pinfunction "1_1") (pintype "passive"))
      (node (ref "U13") (pin "12") (pinfunction "FORCE-_12") (pintype "input"))
    )
    (net (code "55") (name "Net-(U13-ISENSOR)") (class "Default")
      (node (ref "R27") (pin "1") (pinfunction "1_1") (pintype "passive"))
      (node (ref "U13") (pin "6") (pinfunction "REFIN-_6") (pintype "input"))
      (node (ref "U13") (pin "7") (pinfunction "ISENSOR_7") (pintype "input"))
    )
    (net (code "56") (name "Net-(U13-RTDIN+)") (class "Default")
      (node (ref "P13") (pin "4") (pinfunction "4_4") (pintype "passive"))
      (node (ref "U13") (pin "10") (pinfunction "RTDIN+_10") (pintype "input"))
    )
    (net (code "57") (name "Net-(U13-RTDIN-)") (class "Default")
      (node (ref "P13") (pin "2") (pinfunction "2_2") (pintype "passive"))
      (node (ref "U13") (pin "11") (pinfunction "RTDIN-_11") (pintype "input"))
    )
    (net (code "58") (name "Net-(U13-SDO)") (class "Default")
      (node (ref "R24") (pin "1") (pinfunction "1_1") (pintype "passive"))
      (node (ref "U13") (pin "17") (pinfunction "SDO_17") (pintype "output"))
    )
    (net (code "59") (name "Net-(U14-BIAS)") (class "Default")
      (node (ref "R28") (pin "2") (pinfunction "2_2") (pintype "passive"))
      (node (ref "U14") (pin "4") (pinfunction "BIAS_4") (pintype "output"))
      (node (ref "U14") (pin "5") (pinfunction "REFIN+_5") (pintype "input"))
    )
    (net (code "60") (name "Net-(U14-FORCE+)") (class "Default")
      (node (ref "P14") (pin "3") (pinfunction "3_3") (pintype "passive"))
      (node (ref "U14") (pin "8") (pinfunction "FORCE+_8") (pintype "output"))
    )
    (net (code "61") (name "Net-(U14-FORCE-)") (class "Default")
      (node (ref "P14") (pin "1") (pinfunction "1_1") (pintype "passive"))
      (node (ref "U14") (pin "12") (pinfunction "FORCE-_12") (pintype "input"))
    )
    (net (code "62") (name "Net-(U14-ISENSOR)") (class "Default")
      (node (ref "R28") (pin "1") (pinfunction "1_1") (pintype "passive"))
      (node (ref "U14") (pin "6") (pinfunction "REFIN-_6") (pintype "input"))
      (node (ref "U14") (pin "7") (pinfunction "ISENSOR_7") (pintype "input"))
    )
    (net (code "63") (name "Net-(U14-RTDIN+)") (class "Default")
      (node (ref "P14") (pin "4") (pinfunction "4_4") (pintype "passive"))
      (node (ref "U14") (pin "10") (pinfunction "RTDIN+_10") (pintype "input"))
    )
    (net (code "64") (name "Net-(U14-RTDIN-)") (class "Default")
      (node (ref "P14") (pin "2") (pinfunction "2_2") (pintype "passive"))
      (node (ref "U14") (pin "11") (pinfunction "RTDIN-_11") (pintype "input"))
    )
    (net (code "65") (name "Net-(U14-SDO)") (class "Default")
      (node (ref "R25") (pin "1") (pinfunction "1_1") (pintype "passive"))
      (node (ref "U14") (pin "17") (pinfunction "SDO_17") (pintype "output"))
    )
    (net (code "66") (name "Net-(U15-BIAS)") (class "Default")
      (node (ref "R31") (pin "2") (pinfunction "2_2") (pintype "passive"))
      (node (ref "U15") (pin "4") (pinfunction "BIAS_4") (pintype "output"))
      (node (ref "U15") (pin "5") (pinfunction "REFIN+_5") (pintype "input"))
    )
    (net (code "67") (name "Net-(U15-FORCE+)") (class "Default")
      (node (ref "P15") (pin "3") (pinfunction "3_3") (pintype "passive"))
      (node (ref "U15") (pin "8") (pinfunction "FORCE+_8") (pintype "output"))
    )
    (net (code "68") (name "Net-(U15-FORCE-)") (class "Default")
      (node (ref "P15") (pin "1") (pinfunction "1_1") (pintype "passive"))
      (node (ref "U15") (pin "12") (pinfunction "FORCE-_12") (pintype "input"))
    )
    (net (code "69") (name "Net-(U15-ISENSOR)") (class "Default")
      (node (ref "R31") (pin "1") (pinfunction "1_1") (pintype "passive"))
      (node (ref "U15") (pin "6") (pinfunction "REFIN-_6") (pintype "input"))
      (node (ref "U15") (pin "7") (pinfunction "ISENSOR_7") (pintype "input"))
    )
    (net (code "70") (name "Net-(U15-RTDIN+)") (class "Default")
      (node (ref "P15") (pin "4") (pinfunction "4_4") (pintype "passive"))
      (node (ref "U15") (pin "10") (pinfunction "RTDIN+_10") (pintype "input"))
    )
    (net (code "71") (name "Net-(U15-RTDIN-)") (class "Default")
      (node (ref "P15") (pin "2") (pinfunction "2_2") (pintype "passive"))
      (node (ref "U15") (pin "11") (pinfunction "RTDIN-_11") (pintype "input"))
    )
    (net (code "72") (name "Net-(U15-SDO)") (class "Default")
      (node (ref "R29") (pin "1") (pinfunction "1_1") (pintype "passive"))
      (node (ref "U15") (pin "17") (pinfunction "SDO_17") (pintype "output"))
    )
    (net (code "73") (name "Net-(U16-BIAS)") (class "Default")
      (node (ref "R32") (pin "2") (pinfunction "2_2") (pintype "passive"))
      (node (ref "U16") (pin "4") (pinfunction "BIAS_4") (pintype "output"))
      (node (ref "U16") (pin "5") (pinfunction "REFIN+_5") (pintype "input"))
    )
    (net (code "74") (name "Net-(U16-FORCE+)") (class "Default")
      (node (ref "P16") (pin "3") (pinfunction "3_3") (pintype "passive"))
      (node (ref "U16") (pin "8") (pinfunction "FORCE+_8") (pintype "output"))
    )
    (net (code "75") (name "Net-(U16-FORCE-)") (class "Default")
      (node (ref "P16") (pin "1") (pinfunction "1_1") (pintype "passive"))
      (node (ref "U16") (pin "12") (pinfunction "FORCE-_12") (pintype "input"))
    )
    (net (code "76") (name "Net-(U16-ISENSOR)") (class "Default")
      (node (ref "R32") (pin "1") (pinfunction "1_1") (pintype "passive"))
      (node (ref "U16") (pin "6") (pinfunction "REFIN-_6") (pintype "input"))
      (node (ref "U16") (pin "7") (pinfunction "ISENSOR_7") (pintype "input"))
    )
    (net (code "77") (name "Net-(U16-RTDIN+)") (class "Default")
      (node (ref "P16") (pin "4") (pinfunction "4_4") (pintype "passive"))
      (node (ref "U16") (pin "10") (pinfunction "RTDIN+_10") (pintype "input"))
    )
    (net (code "78") (name "Net-(U16-RTDIN-)") (class "Default")
      (node (ref "P16") (pin "2") (pinfunction "2_2") (pintype "passive"))
      (node (ref "U16") (pin "11") (pinfunction "RTDIN-_11") (pintype "input"))
    )
    (net (code "79") (name "Net-(U16-SDO)") (class "Default")
      (node (ref "R30") (pin "1") (pinfunction "1_1") (pintype "passive"))
      (node (ref "U16") (pin "17") (pinfunction "SDO_17") (pintype "output"))
    )
    (net (code "80") (name "unconnected-(U21-N.C.-Pad11)") (class "Default")
      (node (ref "U21") (pin "11") (pinfunction "N.C._11") (pintype "passive+no_connect"))
    )
    (net (code "81") (name "unconnected-(U21-N.C._2-Pad3)") (class "Default")
      (node (ref "U21") (pin "3") (pinfunction "N.C._2_3") (pintype "passive+no_connect"))
    )
  )
)
